# otherblink.net
KiCad netlist of a schematic drawn in EAGLE
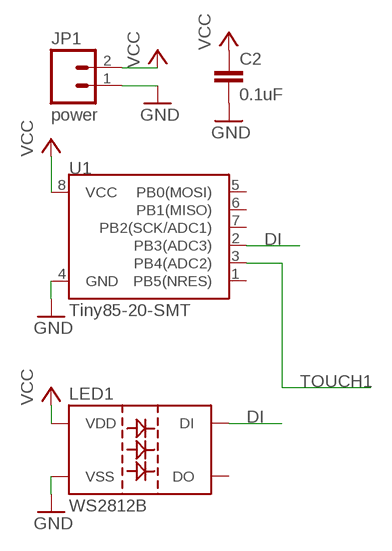
[diagram p0: schematic, sheet 1]

(export (version "E")
  (design (tool "Eeschema 10.0.6"))
  (components
    (comp (ref "C2")
      (value "0.1uF")
      (footprint "eagle-import:0603-CAP")
      (libsource (lib "eagle-import") (part "0.1UF-25V-5%(0603)"))
    )
    (comp (ref "JP1")
      (value "power")
      (footprint "eagle-import:1X02_LONGPADS")
      (libsource (lib "eagle-import") (part "M02PTH3"))
    )
    (comp (ref "LED1")
      (value "WS2812B")
      (footprint "eagle-import:WS2812B")
      (libsource (lib "eagle-import") (part "WS2812B"))
    )
    (comp (ref "U1")
      (value "Tiny85-20-SMT")
      (footprint "eagle-import:SO08-EIAJ")
      (libsource (lib "eagle-import") (part "ATTINY45TINY85-20-SMT"))
    )
  )
  (nets
    (net (code "1") (name "/DI") (class "Default")
      (node (ref "LED1") (pin "4") (pinfunction "DI_4") (pintype "bidirectional"))
      (node (ref "U1") (pin "2") (pinfunction "PB3(ADC3)_2") (pintype "bidirectional"))
    )
    (net (code "2") (name "/TOUCH1") (class "Default")
      (node (ref "U1") (pin "3") (pinfunction "PB4(ADC2)_3") (pintype "bidirectional"))
    )
    (net (code "3") (name "GND") (class "Default")
      (node (ref "C2") (pin "2") (pinfunction "2_2") (pintype "passive"))
      (node (ref "JP1") (pin "1") (pinfunction "1_1") (pintype "passive"))
      (node (ref "LED1") (pin "3") (pinfunction "VSS_3") (pintype "bidirectional"))
      (node (ref "U1") (pin "4") (pinfunction "GND_4") (pintype "bidirectional"))
    )
    (net (code "4") (name "VCC") (class "Default")
      (node (ref "C2") (pin "1") (pinfunction "1_1") (pintype "passive"))
      (node (ref "JP1") (pin "2") (pinfunction "2_2") (pintype "passive"))
      (node (ref "LED1") (pin "1") (pinfunction "VDD_1") (pintype "bidirectional"))
      (node (ref "U1") (pin "8") (pinfunction "VCC_8") (pintype "bidirectional"))
    )
    (net (code "5") (name "unconnected-(LED1-DO-Pad2)") (class "Default")
      (node (ref "LED1") (pin "2") (pinfunction "DO_2") (pintype "bidirectional"))
    )
    (net (code "6") (name "unconnected-(U1-PB0(MOSI)-Pad5)") (class "Default")
      (node (ref "U1") (pin "5") (pinfunction "PB0(MOSI)_5") (pintype "bidirectional"))
    )
    (net (code "7") (name "unconnected-(U1-PB1(MISO)-Pad6)") (class "Default")
      (node (ref "U1") (pin "6") (pinfunction "PB1(MISO)_6") (pintype "bidirectional"))
    )
    (net (code "8") (name "unconnected-(U1-PB2(SCK{slash}ADC1)-Pad7)") (class "Default")
      (node (ref "U1") (pin "7") (pinfunction "PB2(SCK/ADC1)_7") (pintype "bidirectional"))
    )
    (net (code "9") (name "unconnected-(U1-PB5(NRES)-Pad1)") (class "Default")
      (node (ref "U1") (pin "1") (pinfunction "PB5(NRES)_1") (pintype "bidirectional"))
    )
  )
)
